# SCH1_Power.net
KiCad netlist of a schematic drawn in Altium Designer
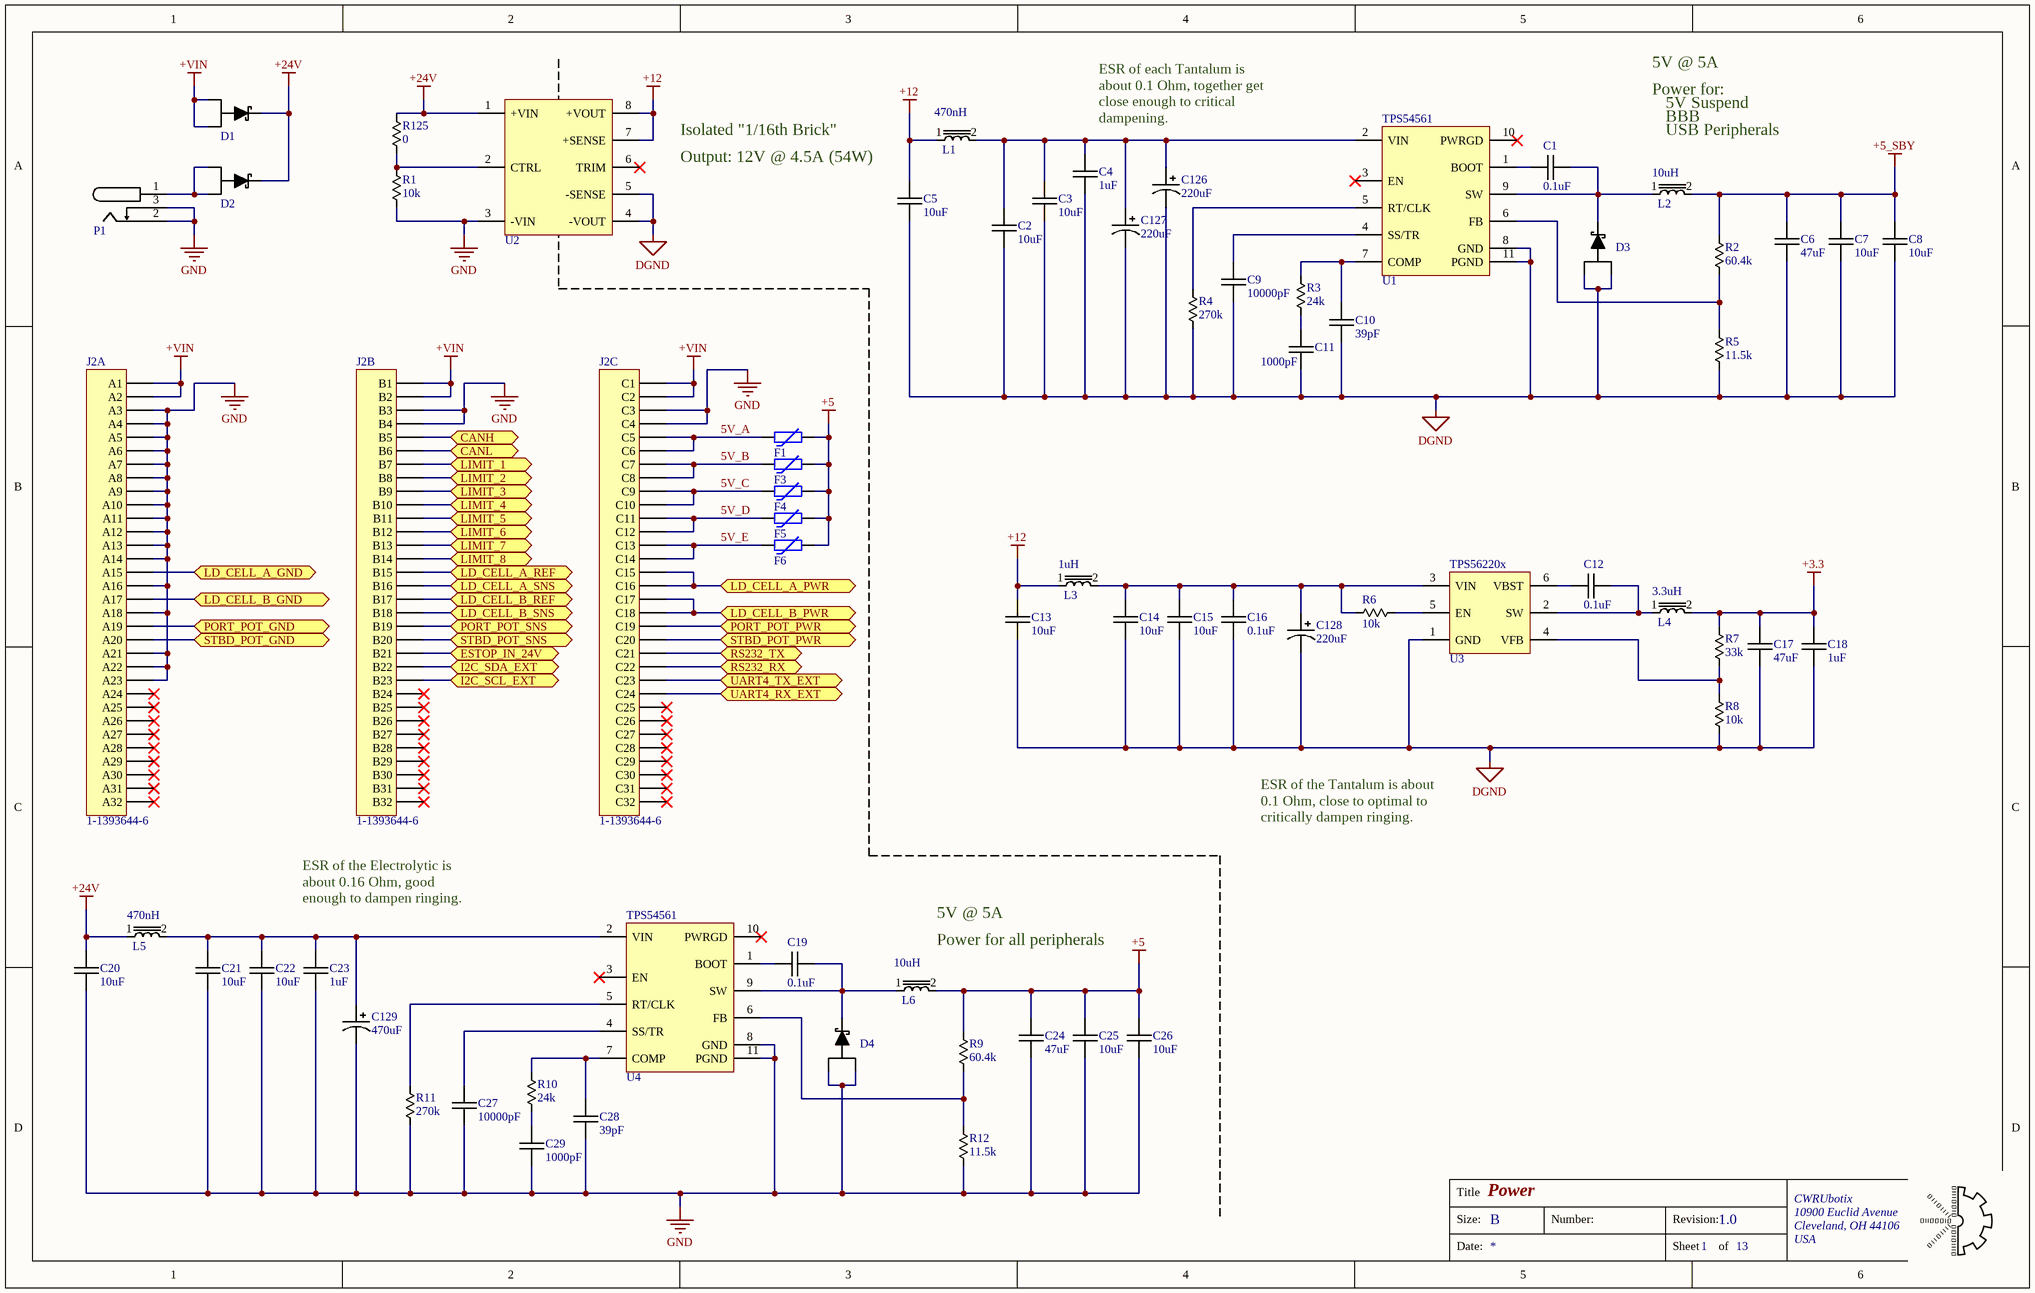
[diagram p0: SCH1_Power.SchDoc]

(export (version "E")
  (design (tool "Eeschema 10.0.6"))
  (components
    (comp (ref "C1")
      (value "0.1uF")
      (footprint "chip_0603")
      (description "CAP, 0.1uF, ±10%, 16V, X7R, 0603")
      (fields (field (name "PART NUMBER") "CAP-00542") (field (name "TOLERANCE") "±10%"))
      (libsource (lib "Capacitors$") (part "CAP-00542"))
    )
    (comp (ref "C2")
      (value "10uF")
      (footprint "chip_1206")
      (description "CAP, 10uF, ±10%, 25V, X7R, 1206")
      (fields (field (name "PART NUMBER") "CAP-00539") (field (name "TOLERANCE") "±10%"))
      (libsource (lib "Capacitors$") (part "CAP-00539"))
    )
    (comp (ref "C3")
      (value "10uF")
      (footprint "chip_1206")
      (description "CAP, 10uF, ±10%, 25V, X7R, 1206")
      (fields (field (name "PART NUMBER") "CAP-00539") (field (name "TOLERANCE") "±10%"))
      (libsource (lib "Capacitors$") (part "CAP-00539"))
    )
    (comp (ref "C4")
      (value "1uF")
      (footprint "chip_0805")
      (description "CAP, 1uF, 10%, 16V, X7R, 0805")
      (fields (field (name "PART NUMBER") "CAP-00110") (field (name "TOLERANCE") "10%"))
      (libsource (lib "Capacitors$") (part "CAP-00110"))
    )
    (comp (ref "C5")
      (value "10uF")
      (footprint "chip_1206")
      (description "CAP, 10uF, ±10%, 25V, X7R, 1206")
      (fields (field (name "PART NUMBER") "CAP-00539") (field (name "TOLERANCE") "±10%"))
      (libsource (lib "Capacitors$") (part "CAP-00539"))
    )
    (comp (ref "C6")
      (value "47uF")
      (footprint "chip_1210")
      (description "CAP, 47uF, ±20%, 6.3V, X7R, 1210")
      (fields (field (name "PART NUMBER") "CAP-00557") (field (name "TOLERANCE") "±20%"))
      (libsource (lib "Capacitors$") (part "CAP-00557"))
    )
    (comp (ref "C7")
      (value "10uF")
      (footprint "chip_1206")
      (description "CAP, 10uF, ±10%, 25V, X7R, 1206")
      (fields (field (name "PART NUMBER") "CAP-00539") (field (name "TOLERANCE") "±10%"))
      (libsource (lib "Capacitors$") (part "CAP-00539"))
    )
    (comp (ref "C8")
      (value "10uF")
      (footprint "chip_1206")
      (description "CAP, 10uF, ±10%, 25V, X7R, 1206")
      (fields (field (name "PART NUMBER") "CAP-00539") (field (name "TOLERANCE") "±10%"))
      (libsource (lib "Capacitors$") (part "CAP-00539"))
    )
    (comp (ref "C9")
      (value "10000pF")
      (footprint "chip_0603")
      (description "CAP, 10000pF, ±10%, 16V, X7R, 0603")
      (fields (field (name "PART NUMBER") "CAP-00543") (field (name "TOLERANCE") "±10%"))
      (libsource (lib "Capacitors$") (part "CAP-00543"))
    )
    (comp (ref "C10")
      (value "39pF")
      (footprint "chip_0603")
      (description "CAP, 39pF, ±1%, 50V, C0G, 0603")
      (fields (field (name "PART NUMBER") "CAP-00423") (field (name "TOLERANCE") "±1%"))
      (libsource (lib "Capacitors$") (part "CAP-00423"))
    )
    (comp (ref "C11")
      (value "1000pF")
      (footprint "chip_0603")
      (description "CAP, 1000pF, ±1%, 50V, C0G, 0603")
      (fields (field (name "PART NUMBER") "CAP-00457") (field (name "TOLERANCE") "±1%"))
      (libsource (lib "Capacitors$") (part "CAP-00457"))
    )
    (comp (ref "C12")
      (value "0.1uF")
      (footprint "chip_0603")
      (description "CAP, 0.1uF, ±10%, 16V, X7R, 0603")
      (fields (field (name "PART NUMBER") "CAP-00542") (field (name "TOLERANCE") "±10%"))
      (libsource (lib "Capacitors$") (part "CAP-00542"))
    )
    (comp (ref "C13")
      (value "10uF")
      (footprint "chip_1206")
      (description "CAP, 10uF, ±10%, 25V, X7R, 1206")
      (fields (field (name "PART NUMBER") "CAP-00539") (field (name "TOLERANCE") "±10%"))
      (libsource (lib "Capacitors$") (part "CAP-00539"))
    )
    (comp (ref "C14")
      (value "10uF")
      (footprint "chip_1206")
      (description "CAP, 10uF, ±10%, 25V, X7R, 1206")
      (fields (field (name "PART NUMBER") "CAP-00539") (field (name "TOLERANCE") "±10%"))
      (libsource (lib "Capacitors$") (part "CAP-00539"))
    )
    (comp (ref "C15")
      (value "10uF")
      (footprint "chip_1206")
      (description "CAP, 10uF, ±10%, 25V, X7R, 1206")
      (fields (field (name "PART NUMBER") "CAP-00539") (field (name "TOLERANCE") "±10%"))
      (libsource (lib "Capacitors$") (part "CAP-00539"))
    )
    (comp (ref "C16")
      (value "0.1uF")
      (footprint "chip_0603")
      (description "CAP, 0.1uF, ±10%, 16V, X7R, 0603")
      (fields (field (name "PART NUMBER") "CAP-00542") (field (name "TOLERANCE") "±10%"))
      (libsource (lib "Capacitors$") (part "CAP-00542"))
    )
    (comp (ref "C17")
      (value "47uF")
      (footprint "chip_1210")
      (description "CAP, 47uF, ±20%, 6.3V, X7R, 1210")
      (fields (field (name "PART NUMBER") "CAP-00557") (field (name "TOLERANCE") "±20%"))
      (libsource (lib "Capacitors$") (part "CAP-00557"))
    )
    (comp (ref "C18")
      (value "1uF")
      (footprint "chip_0805")
      (description "CAP, 1uF, 10%, 16V, X7R, 0805")
      (fields (field (name "PART NUMBER") "CAP-00110") (field (name "TOLERANCE") "10%"))
      (libsource (lib "Capacitors$") (part "CAP-00110"))
    )
    (comp (ref "C19")
      (value "0.1uF")
      (footprint "chip_0603")
      (description "CAP, 0.1uF, ±10%, 16V, X7R, 0603")
      (fields (field (name "PART NUMBER") "CAP-00542") (field (name "TOLERANCE") "±10%"))
      (libsource (lib "Capacitors$") (part "CAP-00542"))
    )
    (comp (ref "C20")
      (value "10uF")
      (footprint "chip_1206")
      (description "CAP, 10uF, ±10%, 25V, X7R, 1206")
      (fields (field (name "PART NUMBER") "CAP-00539") (field (name "TOLERANCE") "±10%"))
      (libsource (lib "Capacitors$") (part "CAP-00539"))
    )
    (comp (ref "C21")
      (value "10uF")
      (footprint "chip_1206")
      (description "CAP, 10uF, ±10%, 25V, X7R, 1206")
      (fields (field (name "PART NUMBER") "CAP-00539") (field (name "TOLERANCE") "±10%"))
      (libsource (lib "Capacitors$") (part "CAP-00539"))
    )
    (comp (ref "C22")
      (value "10uF")
      (footprint "chip_1206")
      (description "CAP, 10uF, ±10%, 25V, X7R, 1206")
      (fields (field (name "PART NUMBER") "CAP-00539") (field (name "TOLERANCE") "±10%"))
      (libsource (lib "Capacitors$") (part "CAP-00539"))
    )
    (comp (ref "C23")
      (value "1uF")
      (footprint "chip_0805")
      (description "CAP, 1uF, 10%, 16V, X7R, 0805")
      (fields (field (name "PART NUMBER") "CAP-00110") (field (name "TOLERANCE") "10%"))
      (libsource (lib "Capacitors$") (part "CAP-00110"))
    )
    (comp (ref "C24")
      (value "47uF")
      (footprint "chip_1210")
      (description "CAP, 47uF, ±20%, 6.3V, X7R, 1210")
      (fields (field (name "PART NUMBER") "CAP-00557") (field (name "TOLERANCE") "±20%"))
      (libsource (lib "Capacitors$") (part "CAP-00557"))
    )
    (comp (ref "C25")
      (value "10uF")
      (footprint "chip_1206")
      (description "CAP, 10uF, ±10%, 25V, X7R, 1206")
      (fields (field (name "PART NUMBER") "CAP-00539") (field (name "TOLERANCE") "±10%"))
      (libsource (lib "Capacitors$") (part "CAP-00539"))
    )
    (comp (ref "C26")
      (value "10uF")
      (footprint "chip_1206")
      (description "CAP, 10uF, ±10%, 25V, X7R, 1206")
      (fields (field (name "PART NUMBER") "CAP-00539") (field (name "TOLERANCE") "±10%"))
      (libsource (lib "Capacitors$") (part "CAP-00539"))
    )
    (comp (ref "C27")
      (value "10000pF")
      (footprint "chip_0603")
      (description "CAP, 10000pF, ±10%, 16V, X7R, 0603")
      (fields (field (name "PART NUMBER") "CAP-00543") (field (name "TOLERANCE") "±10%"))
      (libsource (lib "Capacitors$") (part "CAP-00543"))
    )
    (comp (ref "C28")
      (value "39pF")
      (footprint "chip_0603")
      (description "CAP, 39pF, ±1%, 50V, C0G, 0603")
      (fields (field (name "PART NUMBER") "CAP-00423") (field (name "TOLERANCE") "±1%"))
      (libsource (lib "Capacitors$") (part "CAP-00423"))
    )
    (comp (ref "C29")
      (value "1000pF")
      (footprint "chip_0603")
      (description "CAP, 1000pF, ±1%, 50V, C0G, 0603")
      (fields (field (name "PART NUMBER") "CAP-00457") (field (name "TOLERANCE") "±1%"))
      (libsource (lib "Capacitors$") (part "CAP-00457"))
    )
    (comp (ref "C126")
      (value "220uF")
      (footprint "chip_2917_KEMET_T495")
      (description "CAP, 220uF, ±10%, 16V, Tantalum, 100mOhm, 2917")
      (fields (field (name "PART NUMBER") "CAP-00584") (field (name "TOLERANCE") "±10%"))
      (libsource (lib "Capacitors$") (part "CAP-00584"))
    )
    (comp (ref "C127")
      (value "220uF")
      (footprint "chip_2917_KEMET_T495")
      (description "CAP, 220uF, ±10%, 16V, Tantalum, 100mOhm, 2917")
      (fields (field (name "PART NUMBER") "CAP-00584") (field (name "TOLERANCE") "±10%"))
      (libsource (lib "Capacitors$") (part "CAP-00584"))
    )
    (comp (ref "C128")
      (value "220uF")
      (footprint "chip_2917_KEMET_T495")
      (description "CAP, 220uF, ±10%, 16V, Tantalum, 100mOhm, 2917")
      (fields (field (name "PART NUMBER") "CAP-00584") (field (name "TOLERANCE") "±10%"))
      (libsource (lib "Capacitors$") (part "CAP-00584"))
    )
    (comp (ref "C129")
      (value "470uF")
      (footprint "CAP_SMD_10x10_0")
      (description "CAP, 470uF, ±20%, 25V, Al, SMD, 7000hrs at 105°C")
      (fields (field (name "PART NUMBER") "CAP-00558") (field (name "TOLERANCE") "±20%"))
      (libsource (lib "Capacitors$") (part "CAP-00558"))
    )
    (comp (ref "D1")
      (value "diode_sch_A12C3")
      (footprint "TO-277-3")
      (description "Dio, Schottky, 5A, 0.63V, 60V, TO-227")
      (fields (field (name "PART NUMBER") "DIO-00074") (field (name "MANUFACTURER") "Vishay"))
      (libsource (lib "Diodes$") (part "DIO-00074"))
    )
    (comp (ref "D2")
      (value "diode_sch_A12C3")
      (footprint "TO-277-3")
      (description "Dio, Schottky, 5A, 0.63V, 60V, TO-227")
      (fields (field (name "PART NUMBER") "DIO-00074") (field (name "MANUFACTURER") "Vishay"))
      (libsource (lib "Diodes$") (part "DIO-00074"))
    )
    (comp (ref "D3")
      (value "diode_sch_A12C3")
      (footprint "TO-277-3")
      (description "Dio, Schottky, 5A, 0.63V, 60V, TO-227")
      (fields (field (name "PART NUMBER") "DIO-00074") (field (name "MANUFACTURER") "Vishay"))
      (libsource (lib "Diodes$") (part "DIO-00074"))
    )
    (comp (ref "D4")
      (value "diode_sch_A12C3")
      (footprint "TO-277-3")
      (description "Dio, Schottky, 5A, 0.63V, 60V, TO-227")
      (fields (field (name "PART NUMBER") "DIO-00074") (field (name "MANUFACTURER") "Vishay"))
      (libsource (lib "Diodes$") (part "DIO-00074"))
    )
    (comp (ref "F1")
      (value "PTC_0")
      (footprint "chip_1206")
      (description "PTC Resettable fuse, 6V, 500mA, 1206")
      (fields (field (name "PART NUMBER") "MISC-00008") (field (name "MANUFACTURER") "Eaton"))
      (libsource (lib "Misc$") (part "MISC-00008"))
    )
    (comp (ref "F3")
      (value "PTC_0")
      (footprint "chip_1206")
      (description "PTC Resettable fuse, 6V, 500mA, 1206")
      (fields (field (name "PART NUMBER") "MISC-00008") (field (name "MANUFACTURER") "Eaton"))
      (libsource (lib "Misc$") (part "MISC-00008"))
    )
    (comp (ref "F4")
      (value "PTC_0")
      (footprint "chip_1206")
      (description "PTC Resettable fuse, 6V, 500mA, 1206")
      (fields (field (name "PART NUMBER") "MISC-00008") (field (name "MANUFACTURER") "Eaton"))
      (libsource (lib "Misc$") (part "MISC-00008"))
    )
    (comp (ref "F5")
      (value "PTC_0")
      (footprint "chip_1206")
      (description "PTC Resettable fuse, 6V, 500mA, 1206")
      (fields (field (name "PART NUMBER") "MISC-00008") (field (name "MANUFACTURER") "Eaton"))
      (libsource (lib "Misc$") (part "MISC-00008"))
    )
    (comp (ref "F6")
      (value "PTC_0")
      (footprint "chip_1206")
      (description "PTC Resettable fuse, 6V, 500mA, 1206")
      (fields (field (name "PART NUMBER") "MISC-00008") (field (name "MANUFACTURER") "Eaton"))
      (libsource (lib "Misc$") (part "MISC-00008"))
    )
    (comp (ref "J2")
      (value "1-1393644-6")
      (footprint "TE_CONN_1-1393644-6")
      (description "DIN 41612 Plug, 96-Pos, Male Pins, Right-Angle")
      (fields (field (name "PART NUMBER") "CONN-00084") (field (name "MANUFACTURER") "TE Connectivity"))
      (libsource (lib "Connectors$") (part "CONN-00084"))
    )
    (comp (ref "L1")
      (value "ind_1")
      (footprint "CHIP_1008_IND")
      (description "Ind, 470nH, 4A, 0.027 Ohm, 1008")
      (fields
        (field (name "PART NUMBER") "MAG-00124")
        (field (name "INDUCTANCE") "470nH")
        (field (name "TOLERANCE") "20%")
      )
      (libsource (lib "Magnetics$") (part "MAG-00124"))
    )
    (comp (ref "L2")
      (value "ind_1")
      (footprint "VISHAY_IHLP3232DZ")
      (description "Ind, 10uH, 20%, 5.2A (9A sat.), 0.0599 Ohm")
      (fields
        (field (name "PART NUMBER") "MAG-00106")
        (field (name "INDUCTANCE") "10uH")
        (field (name "TOLERANCE") "20%")
      )
      (libsource (lib "Magnetics$") (part "MAG-00106"))
    )
    (comp (ref "L3")
      (value "ind_1")
      (footprint "chip_0805")
      (description "Ind, 1uH, 20%, 900mA, 0805")
      (fields
        (field (name "PART NUMBER") "MAG-00019")
        (field (name "INDUCTANCE") "1uH")
        (field (name "TOLERANCE") "20%")
      )
      (libsource (lib "Magnetics$") (part "MAG-00019"))
    )
    (comp (ref "L4")
      (value "ind_1")
      (footprint "BOURNS_SRN5040")
      (description "Ind, 3.3uH, 3.3A (3.8A sat.), 0.027 Ohm")
      (fields
        (field (name "PART NUMBER") "MAG-00111")
        (field (name "INDUCTANCE") "3.3uH")
        (field (name "TOLERANCE") "20%")
      )
      (libsource (lib "Magnetics$") (part "MAG-00111"))
    )
    (comp (ref "L5")
      (value "ind_1")
      (footprint "CHIP_1008_IND")
      (description "Ind, 470nH, 4A, 0.027 Ohm, 1008")
      (fields
        (field (name "PART NUMBER") "MAG-00124")
        (field (name "INDUCTANCE") "470nH")
        (field (name "TOLERANCE") "20%")
      )
      (libsource (lib "Magnetics$") (part "MAG-00124"))
    )
    (comp (ref "L6")
      (value "ind_1")
      (footprint "VISHAY_IHLP3232DZ")
      (description "Ind, 10uH, 20%, 5.2A (9A sat.), 0.0599 Ohm")
      (fields
        (field (name "PART NUMBER") "MAG-00106")
        (field (name "INDUCTANCE") "10uH")
        (field (name "TOLERANCE") "20%")
      )
      (libsource (lib "Magnetics$") (part "MAG-00106"))
    )
    (comp (ref "P1")
      (value "conn-barrel_0")
      (footprint "SWITCHCRAFT_RAPC722X")
      (description "Barrel Jack, 2.0x5.5mm IDxOD, Right-Angle")
      (fields (field (name "PART NUMBER") "CONN-00074") (field (name "MANUFACTURER") "Switchcraft"))
      (libsource (lib "Connectors$") (part "CONN-00074"))
    )
    (comp (ref "R1")
      (value "10k")
      (footprint "chip_0603")
      (description "RES SMD 10K OHM 1% 1/4W 0603")
      (fields (field (name "PART NUMBER") "RES-00306") (field (name "TOLERANCE") "1%"))
      (libsource (lib "Resistors$") (part "RES-00306"))
    )
    (comp (ref "R2")
      (value "60.4k")
      (footprint "chip_0805")
      (description "RES SMD 60.4K OHM 1% 1/8W 0805")
      (fields (field (name "PART NUMBER") "RES-00531") (field (name "TOLERANCE") "1%"))
      (libsource (lib "Resistors$") (part "RES-00531"))
    )
    (comp (ref "R3")
      (value "24k")
      (footprint "chip_0603")
      (description "RES SMD 24K OHM 1% 1/4W 0603")
      (fields (field (name "PART NUMBER") "RES-00399") (field (name "TOLERANCE") "1%"))
      (libsource (lib "Resistors$") (part "RES-00399"))
    )
    (comp (ref "R4")
      (value "270k")
      (footprint "chip_0603")
      (description "RES SMD 270K OHM 1% 1/4W 0603")
      (fields (field (name "PART NUMBER") "RES-00405") (field (name "TOLERANCE") "1%"))
      (libsource (lib "Resistors$") (part "RES-00405"))
    )
    (comp (ref "R5")
      (value "11.5k")
      (footprint "chip_0805")
      (description "RES SMD 11.5K OHM 1% 1/8W 0805")
      (fields (field (name "PART NUMBER") "RES-00309") (field (name "TOLERANCE") "1%"))
      (libsource (lib "Resistors$") (part "RES-00309"))
    )
    (comp (ref "R6")
      (value "10k")
      (footprint "chip_0603")
      (description "RES SMD 10K OHM 1% 1/4W 0603")
      (fields (field (name "PART NUMBER") "RES-00306") (field (name "TOLERANCE") "1%"))
      (libsource (lib "Resistors$") (part "RES-00306"))
    )
    (comp (ref "R7")
      (value "33k")
      (footprint "chip_0603")
      (description "RES SMD 33K OHM 1% 1/4W 0603")
      (fields (field (name "PART NUMBER") "RES-00442") (field (name "TOLERANCE") "1%"))
      (libsource (lib "Resistors$") (part "RES-00442"))
    )
    (comp (ref "R8")
      (value "10k")
      (footprint "chip_0603")
      (description "RES SMD 10K OHM 1% 1/4W 0603")
      (fields (field (name "PART NUMBER") "RES-00306") (field (name "TOLERANCE") "1%"))
      (libsource (lib "Resistors$") (part "RES-00306"))
    )
    (comp (ref "R9")
      (value "60.4k")
      (footprint "chip_0805")
      (description "RES SMD 60.4K OHM 1% 1/8W 0805")
      (fields (field (name "PART NUMBER") "RES-00531") (field (name "TOLERANCE") "1%"))
      (libsource (lib "Resistors$") (part "RES-00531"))
    )
    (comp (ref "R10")
      (value "24k")
      (footprint "chip_0603")
      (description "RES SMD 24K OHM 1% 1/4W 0603")
      (fields (field (name "PART NUMBER") "RES-00399") (field (name "TOLERANCE") "1%"))
      (libsource (lib "Resistors$") (part "RES-00399"))
    )
    (comp (ref "R11")
      (value "270k")
      (footprint "chip_0603")
      (description "RES SMD 270K OHM 1% 1/4W 0603")
      (fields (field (name "PART NUMBER") "RES-00405") (field (name "TOLERANCE") "1%"))
      (libsource (lib "Resistors$") (part "RES-00405"))
    )
    (comp (ref "R12")
      (value "11.5k")
      (footprint "chip_0805")
      (description "RES SMD 11.5K OHM 1% 1/8W 0805")
      (fields (field (name "PART NUMBER") "RES-00309") (field (name "TOLERANCE") "1%"))
      (libsource (lib "Resistors$") (part "RES-00309"))
    )
    (comp (ref "R125")
      (value "0")
      (footprint "chip_0805")
      (description "RES SMD 0 OHM 1/8W 0805 Thick Film")
      (fields (field (name "PART NUMBER") "RES-00720") (field (name "TOLERANCE") "Jumper"))
      (libsource (lib "Resistors$") (part "RES-00720"))
    )
    (comp (ref "U1")
      (value "TPS54561")
      (footprint "WSON-10_0")
      (description "REG, SW Buck Adj, 5A, 4.5-60V, 2.5MHz, TPS54561")
      (fields (field (name "PART NUMBER") "PWREG-00033") (field (name "MANUFACTURER") "TI"))
      (libsource (lib "Power Reg$") (part "PWREG-00033"))
    )
    (comp (ref "U2")
      (value "UWS-12/4.5-Q48N-C")
      (footprint "MURATA_UWS")
      (description "Module, Isolated, 1/16 Brick, 12V 4.5A (54W) Negative Logic")
      (fields (field (name "PART NUMBER") "PWREG-00058") (field (name "MANUFACTURER") "Murata"))
      (libsource (lib "Power Reg$") (part "PWREG-00058"))
    )
    (comp (ref "U3")
      (value "TPS56220x")
      (footprint "sot-23-6")
      (description "REG, Synchronous Buck, 2A, 4.5-17V Input, SOT-23-6, TPS562201")
      (fields (field (name "PART NUMBER") "PWREG-00040") (field (name "MANUFACTURER") "TI"))
      (libsource (lib "Power Reg$") (part "PWREG-00040"))
    )
    (comp (ref "U4")
      (value "TPS54561")
      (footprint "WSON-10_0")
      (description "REG, SW Buck Adj, 5A, 4.5-60V, 2.5MHz, TPS54561")
      (fields (field (name "PART NUMBER") "PWREG-00033") (field (name "MANUFACTURER") "TI"))
      (libsource (lib "Power Reg$") (part "PWREG-00033"))
    )
  )
  (nets
    (net (code "1") (name "+3.3") (class "Default")
      (node (ref "C17") (pin "1") (pinfunction "1_1") (pintype "passive"))
      (node (ref "C18") (pin "1") (pinfunction "1_1") (pintype "passive"))
      (node (ref "L4") (pin "2") (pinfunction "2_2") (pintype "passive"))
      (node (ref "R7") (pin "1") (pinfunction "1_1") (pintype "passive"))
    )
    (net (code "2") (name "+5") (class "Default")
      (node (ref "C24") (pin "1") (pinfunction "1_1") (pintype "passive"))
      (node (ref "C25") (pin "1") (pinfunction "1_1") (pintype "passive"))
      (node (ref "C26") (pin "1") (pinfunction "1_1") (pintype "passive"))
      (node (ref "F1") (pin "2") (pinfunction "2_2") (pintype "passive"))
      (node (ref "F3") (pin "2") (pinfunction "2_2") (pintype "passive"))
      (node (ref "F4") (pin "2") (pinfunction "2_2") (pintype "passive"))
      (node (ref "F5") (pin "2") (pinfunction "2_2") (pintype "passive"))
      (node (ref "F6") (pin "2") (pinfunction "2_2") (pintype "passive"))
      (node (ref "L6") (pin "2") (pinfunction "2_2") (pintype "passive"))
      (node (ref "R9") (pin "1") (pinfunction "1_1") (pintype "passive"))
    )
    (net (code "3") (name "+5_SBY") (class "Default")
      (node (ref "C6") (pin "1") (pinfunction "1_1") (pintype "passive"))
      (node (ref "C7") (pin "1") (pinfunction "1_1") (pintype "passive"))
      (node (ref "C8") (pin "1") (pinfunction "1_1") (pintype "passive"))
      (node (ref "L2") (pin "2") (pinfunction "2_2") (pintype "passive"))
      (node (ref "R2") (pin "1") (pinfunction "1_1") (pintype "passive"))
    )
    (net (code "4") (name "+12") (class "Default")
      (node (ref "C13") (pin "1") (pinfunction "1_1") (pintype "passive"))
      (node (ref "C5") (pin "1") (pinfunction "1_1") (pintype "passive"))
      (node (ref "L1") (pin "1") (pinfunction "1_1") (pintype "passive"))
      (node (ref "L3") (pin "1") (pinfunction "1_1") (pintype "passive"))
      (node (ref "U2") (pin "7") (pinfunction "+SENSE_7") (pintype "passive"))
      (node (ref "U2") (pin "8") (pinfunction "+VOUT_8") (pintype "passive"))
    )
    (net (code "5") (name "+24V") (class "Default")
      (node (ref "C20") (pin "1") (pinfunction "1_1") (pintype "passive"))
      (node (ref "D1") (pin "3") (pinfunction "3_3") (pintype "passive"))
      (node (ref "D2") (pin "3") (pinfunction "3_3") (pintype "passive"))
      (node (ref "L5") (pin "1") (pinfunction "1_1") (pintype "passive"))
      (node (ref "R125") (pin "2") (pinfunction "2_2") (pintype "passive"))
      (node (ref "U2") (pin "1") (pinfunction "+VIN_1") (pintype "passive"))
    )
    (net (code "6") (name "+VIN") (class "Default")
      (node (ref "D1") (pin "1") (pinfunction "1_1") (pintype "passive"))
      (node (ref "D1") (pin "2") (pinfunction "2_2") (pintype "passive"))
      (node (ref "J2") (pin "A1") (pinfunction "A1_A1") (pintype "passive"))
      (node (ref "J2") (pin "A2") (pinfunction "A2_A2") (pintype "passive"))
      (node (ref "J2") (pin "B1") (pinfunction "B1_B1") (pintype "passive"))
      (node (ref "J2") (pin "B2") (pinfunction "B2_B2") (pintype "passive"))
      (node (ref "J2") (pin "C1") (pinfunction "C1_C1") (pintype "passive"))
      (node (ref "J2") (pin "C2") (pinfunction "C2_C2") (pintype "passive"))
    )
    (net (code "7") (name "/5V_A") (class "Default")
      (node (ref "F1") (pin "1") (pinfunction "1_1") (pintype "passive"))
      (node (ref "J2") (pin "C5") (pinfunction "C5_C5") (pintype "passive"))
      (node (ref "J2") (pin "C6") (pinfunction "C6_C6") (pintype "passive"))
    )
    (net (code "8") (name "/5V_B") (class "Default")
      (node (ref "F3") (pin "1") (pinfunction "1_1") (pintype "passive"))
      (node (ref "J2") (pin "C7") (pinfunction "C7_C7") (pintype "passive"))
      (node (ref "J2") (pin "C8") (pinfunction "C8_C8") (pintype "passive"))
    )
    (net (code "9") (name "/5V_C") (class "Default")
      (node (ref "F4") (pin "1") (pinfunction "1_1") (pintype "passive"))
      (node (ref "J2") (pin "C10") (pinfunction "C10_C10") (pintype "passive"))
      (node (ref "J2") (pin "C9") (pinfunction "C9_C9") (pintype "passive"))
    )
    (net (code "10") (name "/5V_D") (class "Default")
      (node (ref "F5") (pin "1") (pinfunction "1_1") (pintype "passive"))
      (node (ref "J2") (pin "C11") (pinfunction "C11_C11") (pintype "passive"))
      (node (ref "J2") (pin "C12") (pinfunction "C12_C12") (pintype "passive"))
    )
    (net (code "11") (name "/5V_E") (class "Default")
      (node (ref "F6") (pin "1") (pinfunction "1_1") (pintype "passive"))
      (node (ref "J2") (pin "C13") (pinfunction "C13_C13") (pintype "passive"))
      (node (ref "J2") (pin "C14") (pinfunction "C14_C14") (pintype "passive"))
    )
    (net (code "12") (name "/CANH") (class "Default")
      (node (ref "J2") (pin "B5") (pinfunction "B5_B5") (pintype "passive"))
    )
    (net (code "13") (name "/CANL") (class "Default")
      (node (ref "J2") (pin "B6") (pinfunction "B6_B6") (pintype "passive"))
    )
    (net (code "14") (name "/ESTOP_IN_24V") (class "Default")
      (node (ref "J2") (pin "B21") (pinfunction "B21_B21") (pintype "passive"))
    )
    (net (code "15") (name "/I2C_SCL_EXT") (class "Default")
      (node (ref "J2") (pin "B23") (pinfunction "B23_B23") (pintype "passive"))
    )
    (net (code "16") (name "/I2C_SDA_EXT") (class "Default")
      (node (ref "J2") (pin "B22") (pinfunction "B22_B22") (pintype "passive"))
    )
    (net (code "17") (name "/LD_CELL_A_GND") (class "Default")
      (node (ref "J2") (pin "A15") (pinfunction "A15_A15") (pintype "passive"))
    )
    (net (code "18") (name "/LD_CELL_A_PWR") (class "Default")
      (node (ref "J2") (pin "C15") (pinfunction "C15_C15") (pintype "passive"))
      (node (ref "J2") (pin "C16") (pinfunction "C16_C16") (pintype "passive"))
    )
    (net (code "19") (name "/LD_CELL_A_REF") (class "Default")
      (node (ref "J2") (pin "B15") (pinfunction "B15_B15") (pintype "passive"))
    )
    (net (code "20") (name "/LD_CELL_A_SNS") (class "Default")
      (node (ref "J2") (pin "B16") (pinfunction "B16_B16") (pintype "passive"))
    )
    (net (code "21") (name "/LD_CELL_B_GND") (class "Default")
      (node (ref "J2") (pin "A17") (pinfunction "A17_A17") (pintype "passive"))
    )
    (net (code "22") (name "/LD_CELL_B_PWR") (class "Default")
      (node (ref "J2") (pin "C17") (pinfunction "C17_C17") (pintype "passive"))
      (node (ref "J2") (pin "C18") (pinfunction "C18_C18") (pintype "passive"))
    )
    (net (code "23") (name "/LD_CELL_B_REF") (class "Default")
      (node (ref "J2") (pin "B17") (pinfunction "B17_B17") (pintype "passive"))
    )
    (net (code "24") (name "/LD_CELL_B_SNS") (class "Default")
      (node (ref "J2") (pin "B18") (pinfunction "B18_B18") (pintype "passive"))
    )
    (net (code "25") (name "/LIMIT_1") (class "Default")
      (node (ref "J2") (pin "B7") (pinfunction "B7_B7") (pintype "passive"))
    )
    (net (code "26") (name "/LIMIT_2") (class "Default")
      (node (ref "J2") (pin "B8") (pinfunction "B8_B8") (pintype "passive"))
    )
    (net (code "27") (name "/LIMIT_3") (class "Default")
      (node (ref "J2") (pin "B9") (pinfunction "B9_B9") (pintype "passive"))
    )
    (net (code "28") (name "/LIMIT_4") (class "Default")
      (node (ref "J2") (pin "B10") (pinfunction "B10_B10") (pintype "passive"))
    )
    (net (code "29") (name "/LIMIT_5") (class "Default")
      (node (ref "J2") (pin "B11") (pinfunction "B11_B11") (pintype "passive"))
    )
    (net (code "30") (name "/LIMIT_6") (class "Default")
      (node (ref "J2") (pin "B12") (pinfunction "B12_B12") (pintype "passive"))
    )
    (net (code "31") (name "/LIMIT_7") (class "Default")
      (node (ref "J2") (pin "B13") (pinfunction "B13_B13") (pintype "passive"))
    )
    (net (code "32") (name "/LIMIT_8") (class "Default")
      (node (ref "J2") (pin "B14") (pinfunction "B14_B14") (pintype "passive"))
    )
    (net (code "33") (name "/PORT_POT_GND") (class "Default")
      (node (ref "J2") (pin "A19") (pinfunction "A19_A19") (pintype "passive"))
    )
    (net (code "34") (name "/PORT_POT_PWR") (class "Default")
      (node (ref "J2") (pin "C19") (pinfunction "C19_C19") (pintype "passive"))
    )
    (net (code "35") (name "/PORT_POT_SNS") (class "Default")
      (node (ref "J2") (pin "B19") (pinfunction "B19_B19") (pintype "passive"))
    )
    (net (code "36") (name "/RS232_RX") (class "Default")
      (node (ref "J2") (pin "C22") (pinfunction "C22_C22") (pintype "passive"))
    )
    (net (code "37") (name "/RS232_TX") (class "Default")
      (node (ref "J2") (pin "C21") (pinfunction "C21_C21") (pintype "passive"))
    )
    (net (code "38") (name "/STBD_POT_GND") (class "Default")
      (node (ref "J2") (pin "A20") (pinfunction "A20_A20") (pintype "passive"))
    )
    (net (code "39") (name "/STBD_POT_PWR") (class "Default")
      (node (ref "J2") (pin "C20") (pinfunction "C20_C20") (pintype "passive"))
    )
    (net (code "40") (name "/STBD_POT_SNS") (class "Default")
      (node (ref "J2") (pin "B20") (pinfunction "B20_B20") (pintype "passive"))
    )
    (net (code "41") (name "/UART4_RX_EXT") (class "Default")
      (node (ref "J2") (pin "C24") (pinfunction "C24_C24") (pintype "passive"))
    )
    (net (code "42") (name "/UART4_TX_EXT") (class "Default")
      (node (ref "J2") (pin "C23") (pinfunction "C23_C23") (pintype "passive"))
    )
    (net (code "43") (name "DGND") (class "Default")
      (node (ref "C10") (pin "2") (pinfunction "2_2") (pintype "passive"))
      (node (ref "C11") (pin "2") (pinfunction "2_2") (pintype "passive"))
      (node (ref "C126") (pin "2") (pinfunction "2_2") (pintype "passive"))
      (node (ref "C127") (pin "2") (pinfunction "2_2") (pintype "passive"))
      (node (ref "C128") (pin "2") (pinfunction "2_2") (pintype "passive"))
      (node (ref "C13") (pin "2") (pinfunction "2_2") (pintype "passive"))
      (node (ref "C14") (pin "2") (pinfunction "2_2") (pintype "passive"))
      (node (ref "C15") (pin "2") (pinfunction "2_2") (pintype "passive"))
      (node (ref "C16") (pin "2") (pinfunction "2_2") (pintype "passive"))
      (node (ref "C17") (pin "2") (pinfunction "2_2") (pintype "passive"))
      (node (ref "C18") (pin "2") (pinfunction "2_2") (pintype "passive"))
      (node (ref "C2") (pin "2") (pinfunction "2_2") (pintype "passive"))
      (node (ref "C3") (pin "2") (pinfunction "2_2") (pintype "passive"))
      (node (ref "C4") (pin "2") (pinfunction "2_2") (pintype "passive"))
      (node (ref "C5") (pin "2") (pinfunction "2_2") (pintype "passive"))
      (node (ref "C6") (pin "2") (pinfunction "2_2") (pintype "passive"))
      (node (ref "C7") (pin "2") (pinfunction "2_2") (pintype "passive"))
      (node (ref "C8") (pin "2") (pinfunction "2_2") (pintype "passive"))
      (node (ref "C9") (pin "2") (pinfunction "2_2") (pintype "passive"))
      (node (ref "D3") (pin "1") (pinfunction "1_1") (pintype "passive"))
      (node (ref "D3") (pin "2") (pinfunction "2_2") (pintype "passive"))
      (node (ref "R4") (pin "2") (pinfunction "2_2") (pintype "passive"))
      (node (ref "R5") (pin "2") (pinfunction "2_2") (pintype "passive"))
      (node (ref "R8") (pin "2") (pinfunction "2_2") (pintype "passive"))
      (node (ref "U1") (pin "11") (pinfunction "PGND_11") (pintype "passive"))
      (node (ref "U1") (pin "8") (pinfunction "GND_8") (pintype "passive"))
      (node (ref "U2") (pin "4") (pinfunction "-VOUT_4") (pintype "passive"))
      (node (ref "U2") (pin "5") (pinfunction "-SENSE_5") (pintype "passive"))
      (node (ref "U3") (pin "1") (pinfunction "GND_1") (pintype "passive"))
    )
    (net (code "44") (name "GND") (class "Default")
      (node (ref "C129") (pin "2") (pinfunction "2_2") (pintype "passive"))
      (node (ref "C20") (pin "2") (pinfunction "2_2") (pintype "passive"))
      (node (ref "C21") (pin "2") (pinfunction "2_2") (pintype "passive"))
      (node (ref "C22") (pin "2") (pinfunction "2_2") (pintype "passive"))
      (node (ref "C23") (pin "2") (pinfunction "2_2") (pintype "passive"))
      (node (ref "C24") (pin "2") (pinfunction "2_2") (pintype "passive"))
      (node (ref "C25") (pin "2") (pinfunction "2_2") (pintype "passive"))
      (node (ref "C26") (pin "2") (pinfunction "2_2") (pintype "passive"))
      (node (ref "C27") (pin "2") (pinfunction "2_2") (pintype "passive"))
      (node (ref "C28") (pin "2") (pinfunction "2_2") (pintype "passive"))
      (node (ref "C29") (pin "2") (pinfunction "2_2") (pintype "passive"))
      (node (ref "D4") (pin "1") (pinfunction "1_1") (pintype "passive"))
      (node (ref "D4") (pin "2") (pinfunction "2_2") (pintype "passive"))
      (node (ref "J2") (pin "A10") (pinfunction "A10_A10") (pintype "passive"))
      (node (ref "J2") (pin "A11") (pinfunction "A11_A11") (pintype "passive"))
      (node (ref "J2") (pin "A12") (pinfunction "A12_A12") (pintype "passive"))
      (node (ref "J2") (pin "A13") (pinfunction "A13_A13") (pintype "passive"))
      (node (ref "J2") (pin "A14") (pinfunction "A14_A14") (pintype "passive"))
      (node (ref "J2") (pin "A16") (pinfunction "A16_A16") (pintype "passive"))
      (node (ref "J2") (pin "A18") (pinfunction "A18_A18") (pintype "passive"))
      (node (ref "J2") (pin "A21") (pinfunction "A21_A21") (pintype "passive"))
      (node (ref "J2") (pin "A22") (pinfunction "A22_A22") (pintype "passive"))
      (node (ref "J2") (pin "A23") (pinfunction "A23_A23") (pintype "passive"))
      (node (ref "J2") (pin "A3") (pinfunction "A3_A3") (pintype "passive"))
      (node (ref "J2") (pin "A4") (pinfunction "A4_A4") (pintype "passive"))
      (node (ref "J2") (pin "A5") (pinfunction "A5_A5") (pintype "passive"))
      (node (ref "J2") (pin "A6") (pinfunction "A6_A6") (pintype "passive"))
      (node (ref "J2") (pin "A7") (pinfunction "A7_A7") (pintype "passive"))
      (node (ref "J2") (pin "A8") (pinfunction "A8_A8") (pintype "passive"))
      (node (ref "J2") (pin "A9") (pinfunction "A9_A9") (pintype "passive"))
      (node (ref "J2") (pin "B3") (pinfunction "B3_B3") (pintype "passive"))
      (node (ref "J2") (pin "B4") (pinfunction "B4_B4") (pintype "passive"))
      (node (ref "J2") (pin "C3") (pinfunction "C3_C3") (pintype "passive"))
      (node (ref "J2") (pin "C4") (pinfunction "C4_C4") (pintype "passive"))
      (node (ref "P1") (pin "2") (pinfunction "GND_2") (pintype "passive"))
      (node (ref "P1") (pin "3") (pintype "passive"))
      (node (ref "R1") (pin "2") (pinfunction "2_2") (pintype "passive"))
      (node (ref "R11") (pin "2") (pinfunction "2_2") (pintype "passive"))
      (node (ref "R12") (pin "2") (pinfunction "2_2") (pintype "passive"))
      (node (ref "U2") (pin "3") (pinfunction "-VIN_3") (pintype "passive"))
      (node (ref "U4") (pin "11") (pinfunction "PGND_11") (pintype "passive"))
      (node (ref "U4") (pin "8") (pinfunction "GND_8") (pintype "passive"))
    )
    (net (code "45") (name "Net-(C11-Pad1)") (class "Default")
      (node (ref "C11") (pin "1") (pinfunction "1_1") (pintype "passive"))
      (node (ref "R3") (pin "2") (pinfunction "2_2") (pintype "passive"))
    )
    (net (code "46") (name "Net-(C29-Pad1)") (class "Default")
      (node (ref "C29") (pin "1") (pinfunction "1_1") (pintype "passive"))
      (node (ref "R10") (pin "2") (pinfunction "2_2") (pintype "passive"))
    )
    (net (code "47") (name "Net-(P1-VCC)") (class "Default")
      (node (ref "D2") (pin "1") (pinfunction "1_1") (pintype "passive"))
      (node (ref "D2") (pin "2") (pinfunction "2_2") (pintype "passive"))
      (node (ref "P1") (pin "1") (pinfunction "VCC_1") (pintype "passive"))
    )
    (net (code "48") (name "Net-(U1-BOOT)") (class "Default")
      (node (ref "C1") (pin "1") (pinfunction "1_1") (pintype "passive"))
      (node (ref "U1") (pin "1") (pinfunction "BOOT_1") (pintype "passive"))
    )
    (net (code "49") (name "Net-(U1-COMP)") (class "Default")
      (node (ref "C10") (pin "1") (pinfunction "1_1") (pintype "passive"))
      (node (ref "R3") (pin "1") (pinfunction "1_1") (pintype "passive"))
      (node (ref "U1") (pin "7") (pinfunction "COMP_7") (pintype "passive"))
    )
    (net (code "50") (name "Net-(U1-FB)") (class "Default")
      (node (ref "R2") (pin "2") (pinfunction "2_2") (pintype "passive"))
      (node (ref "R5") (pin "1") (pinfunction "1_1") (pintype "passive"))
      (node (ref "U1") (pin "6") (pinfunction "FB_6") (pintype "passive"))
    )
    (net (code "51") (name "Net-(U1-RT{slash}CLK)") (class "Default")
      (node (ref "R4") (pin "1") (pinfunction "1_1") (pintype "passive"))
      (node (ref "U1") (pin "5") (pinfunction "RT/CLK_5") (pintype "passive"))
    )
    (net (code "52") (name "Net-(U1-SS{slash}TR)") (class "Default")
      (node (ref "C9") (pin "1") (pinfunction "1_1") (pintype "passive"))
      (node (ref "U1") (pin "4") (pinfunction "SS/TR_4") (pintype "passive"))
    )
    (net (code "53") (name "Net-(U1-SW)") (class "Default")
      (node (ref "C1") (pin "2") (pinfunction "2_2") (pintype "passive"))
      (node (ref "D3") (pin "3") (pinfunction "3_3") (pintype "passive"))
      (node (ref "L2") (pin "1") (pinfunction "1_1") (pintype "passive"))
      (node (ref "U1") (pin "9") (pinfunction "SW_9") (pintype "passive"))
    )
    (net (code "54") (name "Net-(U1-VIN)") (class "Default")
      (node (ref "C126") (pin "1") (pinfunction "1_1") (pintype "passive"))
      (node (ref "C127") (pin "1") (pinfunction "1_1") (pintype "passive"))
      (node (ref "C2") (pin "1") (pinfunction "1_1") (pintype "passive"))
      (node (ref "C3") (pin "1") (pinfunction "1_1") (pintype "passive"))
      (node (ref "C4") (pin "1") (pinfunction "1_1") (pintype "passive"))
      (node (ref "L1") (pin "2") (pinfunction "2_2") (pintype "passive"))
      (node (ref "U1") (pin "2") (pinfunction "VIN_2") (pintype "passive"))
    )
    (net (code "55") (name "Net-(U2-CTRL)") (class "Default")
      (node (ref "R1") (pin "1") (pinfunction "1_1") (pintype "passive"))
      (node (ref "R125") (pin "1") (pinfunction "1_1") (pintype "passive"))
      (node (ref "U2") (pin "2") (pinfunction "CTRL_2") (pintype "passive"))
    )
    (net (code "56") (name "Net-(U3-EN)") (class "Default")
      (node (ref "R6") (pin "1") (pinfunction "1_1") (pintype "passive"))
      (node (ref "U3") (pin "5") (pinfunction "EN_5") (pintype "passive"))
    )
    (net (code "57") (name "Net-(U3-SW)") (class "Default")
      (node (ref "C12") (pin "2") (pinfunction "2_2") (pintype "passive"))
      (node (ref "L4") (pin "1") (pinfunction "1_1") (pintype "passive"))
      (node (ref "U3") (pin "2") (pinfunction "SW_2") (pintype "passive"))
    )
    (net (code "58") (name "Net-(U3-VBST)") (class "Default")
      (node (ref "C12") (pin "1") (pinfunction "1_1") (pintype "passive"))
      (node (ref "U3") (pin "6") (pinfunction "VBST_6") (pintype "passive"))
    )
    (net (code "59") (name "Net-(U3-VFB)") (class "Default")
      (node (ref "R7") (pin "2") (pinfunction "2_2") (pintype "passive"))
      (node (ref "R8") (pin "1") (pinfunction "1_1") (pintype "passive"))
      (node (ref "U3") (pin "4") (pinfunction "VFB_4") (pintype "passive"))
    )
    (net (code "60") (name "Net-(U3-VIN)") (class "Default")
      (node (ref "C128") (pin "1") (pinfunction "1_1") (pintype "passive"))
      (node (ref "C14") (pin "1") (pinfunction "1_1") (pintype "passive"))
      (node (ref "C15") (pin "1") (pinfunction "1_1") (pintype "passive"))
      (node (ref "C16") (pin "1") (pinfunction "1_1") (pintype "passive"))
      (node (ref "L3") (pin "2") (pinfunction "2_2") (pintype "passive"))
      (node (ref "R6") (pin "2") (pinfunction "2_2") (pintype "passive"))
      (node (ref "U3") (pin "3") (pinfunction "VIN_3") (pintype "passive"))
    )
    (net (code "61") (name "Net-(U4-BOOT)") (class "Default")
      (node (ref "C19") (pin "1") (pinfunction "1_1") (pintype "passive"))
      (node (ref "U4") (pin "1") (pinfunction "BOOT_1") (pintype "passive"))
    )
    (net (code "62") (name "Net-(U4-COMP)") (class "Default")
      (node (ref "C28") (pin "1") (pinfunction "1_1") (pintype "passive"))
      (node (ref "R10") (pin "1") (pinfunction "1_1") (pintype "passive"))
      (node (ref "U4") (pin "7") (pinfunction "COMP_7") (pintype "passive"))
    )
    (net (code "63") (name "Net-(U4-FB)") (class "Default")
      (node (ref "R12") (pin "1") (pinfunction "1_1") (pintype "passive"))
      (node (ref "R9") (pin "2") (pinfunction "2_2") (pintype "passive"))
      (node (ref "U4") (pin "6") (pinfunction "FB_6") (pintype "passive"))
    )
    (net (code "64") (name "Net-(U4-RT{slash}CLK)") (class "Default")
      (node (ref "R11") (pin "1") (pinfunction "1_1") (pintype "passive"))
      (node (ref "U4") (pin "5") (pinfunction "RT/CLK_5") (pintype "passive"))
    )
    (net (code "65") (name "Net-(U4-SS{slash}TR)") (class "Default")
      (node (ref "C27") (pin "1") (pinfunction "1_1") (pintype "passive"))
      (node (ref "U4") (pin "4") (pinfunction "SS/TR_4") (pintype "passive"))
    )
    (net (code "66") (name "Net-(U4-SW)") (class "Default")
      (node (ref "C19") (pin "2") (pinfunction "2_2") (pintype "passive"))
      (node (ref "D4") (pin "3") (pinfunction "3_3") (pintype "passive"))
      (node (ref "L6") (pin "1") (pinfunction "1_1") (pintype "passive"))
      (node (ref "U4") (pin "9") (pinfunction "SW_9") (pintype "passive"))
    )
    (net (code "67") (name "Net-(U4-VIN)") (class "Default")
      (node (ref "C129") (pin "1") (pinfunction "1_1") (pintype "passive"))
      (node (ref "C21") (pin "1") (pinfunction "1_1") (pintype "passive"))
      (node (ref "C22") (pin "1") (pinfunction "1_1") (pintype "passive"))
      (node (ref "C23") (pin "1") (pinfunction "1_1") (pintype "passive"))
      (node (ref "L5") (pin "2") (pinfunction "2_2") (pintype "passive"))
      (node (ref "U4") (pin "2") (pinfunction "VIN_2") (pintype "passive"))
    )
    (net (code "68") (name "unconnected-(J2-PadA24)") (class "Default")
      (node (ref "J2") (pin "A24") (pinfunction "A24_A24") (pintype "passive+no_connect"))
    )
    (net (code "69") (name "unconnected-(J2-PadA25)") (class "Default")
      (node (ref "J2") (pin "A25") (pinfunction "A25_A25") (pintype "passive+no_connect"))
    )
    (net (code "70") (name "unconnected-(J2-PadA26)") (class "Default")
      (node (ref "J2") (pin "A26") (pinfunction "A26_A26") (pintype "passive+no_connect"))
    )
    (net (code "71") (name "unconnected-(J2-PadA27)") (class "Default")
      (node (ref "J2") (pin "A27") (pinfunction "A27_A27") (pintype "passive+no_connect"))
    )
    (net (code "72") (name "unconnected-(J2-PadA28)") (class "Default")
      (node (ref "J2") (pin "A28") (pinfunction "A28_A28") (pintype "passive+no_connect"))
    )
    (net (code "73") (name "unconnected-(J2-PadA29)") (class "Default")
      (node (ref "J2") (pin "A29") (pinfunction "A29_A29") (pintype "passive+no_connect"))
    )
    (net (code "74") (name "unconnected-(J2-PadA30)") (class "Default")
      (node (ref "J2") (pin "A30") (pinfunction "A30_A30") (pintype "passive+no_connect"))
    )
    (net (code "75") (name "unconnected-(J2-PadA31)") (class "Default")
      (node (ref "J2") (pin "A31") (pinfunction "A31_A31") (pintype "passive+no_connect"))
    )
    (net (code "76") (name "unconnected-(J2-PadA32)") (class "Default")
      (node (ref "J2") (pin "A32") (pinfunction "A32_A32") (pintype "passive+no_connect"))
    )
    (net (code "77") (name "unconnected-(J2-PadB24)") (class "Default")
      (node (ref "J2") (pin "B24") (pinfunction "B24_B24") (pintype "passive+no_connect"))
    )
    (net (code "78") (name "unconnected-(J2-PadB25)") (class "Default")
      (node (ref "J2") (pin "B25") (pinfunction "B25_B25") (pintype "passive+no_connect"))
    )
    (net (code "79") (name "unconnected-(J2-PadB26)") (class "Default")
      (node (ref "J2") (pin "B26") (pinfunction "B26_B26") (pintype "passive+no_connect"))
    )
    (net (code "80") (name "unconnected-(J2-PadB27)") (class "Default")
      (node (ref "J2") (pin "B27") (pinfunction "B27_B27") (pintype "passive+no_connect"))
    )
    (net (code "81") (name "unconnected-(J2-PadB28)") (class "Default")
      (node (ref "J2") (pin "B28") (pinfunction "B28_B28") (pintype "passive+no_connect"))
    )
    (net (code "82") (name "unconnected-(J2-PadB29)") (class "Default")
      (node (ref "J2") (pin "B29") (pinfunction "B29_B29") (pintype "passive+no_connect"))
    )
    (net (code "83") (name "unconnected-(J2-PadB30)") (class "Default")
      (node (ref "J2") (pin "B30") (pinfunction "B30_B30") (pintype "passive+no_connect"))
    )
    (net (code "84") (name "unconnected-(J2-PadB31)") (class "Default")
      (node (ref "J2") (pin "B31") (pinfunction "B31_B31") (pintype "passive+no_connect"))
    )
    (net (code "85") (name "unconnected-(J2-PadB32)") (class "Default")
      (node (ref "J2") (pin "B32") (pinfunction "B32_B32") (pintype "passive+no_connect"))
    )
    (net (code "86") (name "unconnected-(J2-PadC25)") (class "Default")
      (node (ref "J2") (pin "C25") (pinfunction "C25_C25") (pintype "passive+no_connect"))
    )
    (net (code "87") (name "unconnected-(J2-PadC26)") (class "Default")
      (node (ref "J2") (pin "C26") (pinfunction "C26_C26") (pintype "passive+no_connect"))
    )
    (net (code "88") (name "unconnected-(J2-PadC27)") (class "Default")
      (node (ref "J2") (pin "C27") (pinfunction "C27_C27") (pintype "passive+no_connect"))
    )
    (net (code "89") (name "unconnected-(J2-PadC28)") (class "Default")
      (node (ref "J2") (pin "C28") (pinfunction "C28_C28") (pintype "passive+no_connect"))
    )
    (net (code "90") (name "unconnected-(J2-PadC29)") (class "Default")
      (node (ref "J2") (pin "C29") (pinfunction "C29_C29") (pintype "passive+no_connect"))
    )
    (net (code "91") (name "unconnected-(J2-PadC30)") (class "Default")
      (node (ref "J2") (pin "C30") (pinfunction "C30_C30") (pintype "passive+no_connect"))
    )
    (net (code "92") (name "unconnected-(J2-PadC31)") (class "Default")
      (node (ref "J2") (pin "C31") (pinfunction "C31_C31") (pintype "passive+no_connect"))
    )
    (net (code "93") (name "unconnected-(J2-PadC32)") (class "Default")
      (node (ref "J2") (pin "C32") (pinfunction "C32_C32") (pintype "passive+no_connect"))
    )
    (net (code "94") (name "unconnected-(U1-EN-Pad3)") (class "Default")
      (node (ref "U1") (pin "3") (pinfunction "EN_3") (pintype "passive+no_connect"))
    )
    (net (code "95") (name "unconnected-(U1-PWRGD-Pad10)") (class "Default")
      (node (ref "U1") (pin "10") (pinfunction "PWRGD_10") (pintype "passive+no_connect"))
    )
    (net (code "96") (name "unconnected-(U2-TRIM-Pad6)") (class "Default")
      (node (ref "U2") (pin "6") (pinfunction "TRIM_6") (pintype "passive+no_connect"))
    )
    (net (code "97") (name "unconnected-(U4-EN-Pad3)") (class "Default")
      (node (ref "U4") (pin "3") (pinfunction "EN_3") (pintype "passive+no_connect"))
    )
    (net (code "98") (name "unconnected-(U4-PWRGD-Pad10)") (class "Default")
      (node (ref "U4") (pin "10") (pinfunction "PWRGD_10") (pintype "passive+no_connect"))
    )
  )
)
